# eth_lan8742a_phy.net
KiCad netlist of a schematic drawn in Altium Designer
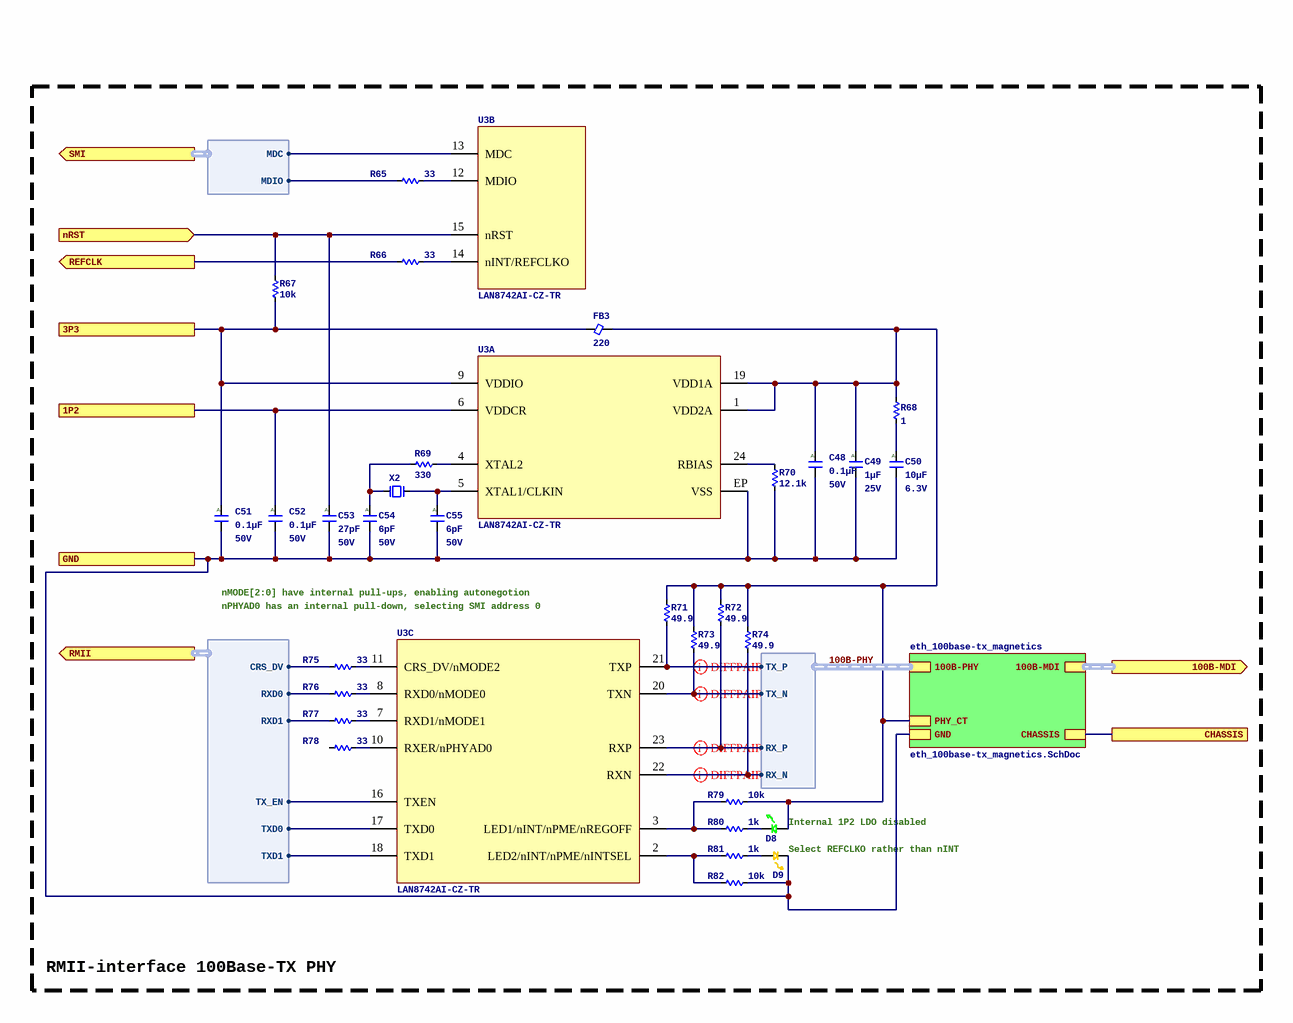
[diagram p0: eth_lan8742a_phy.SchDoc]

(export (version "E")
  (design (tool "Eeschema 10.0.6"))
  (components
    (comp (ref "C48")
      (value "CGA2B3X7R1H104M050BB")
      (footprint "C0402_0.55MM")
      (description "CAP CER 0.1UF 50V X7R 0402")
      (fields
        (field (name "CAPACITANCE") "0.1µF")
        (field (name "VOLTAGE - RATED") "50V")
        (field (name "TOLERANCE") "±20%")
        (field (name "MANUFACTURER") "TDK Corporation")
      )
      (libsource (lib "sscp") (part "__template_cap_auto"))
    )
    (comp (ref "C49")
      (value "CGJ3E1X7R1E105K080AC")
      (footprint "C0603_0.80MM")
      (description "CAP CER 1UF 25V X7R 0603")
      (fields
        (field (name "CAPACITANCE") "1µF")
        (field (name "VOLTAGE - RATED") "25V")
        (field (name "TOLERANCE") "±10%")
        (field (name "MANUFACTURER") "TDK Corporation")
      )
      (libsource (lib "sscp") (part "__template_cap_auto"))
    )
    (comp (ref "C50")
      (value "CGA4J1X7R0J106M125AC")
      (footprint "C0805_1.45MM")
      (description "CAP CER 10UF 6.3V X7R 0805")
      (fields
        (field (name "CAPACITANCE") "10µF")
        (field (name "VOLTAGE - RATED") "6.3V")
        (field (name "TOLERANCE") "±20%")
        (field (name "MANUFACTURER") "TDK Corporation")
      )
      (libsource (lib "sscp") (part "__template_cap_auto"))
    )
    (comp (ref "C51")
      (value "CGA2B3X7R1H104M050BB")
      (footprint "C0402_0.55MM")
      (description "CAP CER 0.1UF 50V X7R 0402")
      (fields
        (field (name "CAPACITANCE") "0.1µF")
        (field (name "VOLTAGE - RATED") "50V")
        (field (name "TOLERANCE") "±20%")
        (field (name "MANUFACTURER") "TDK Corporation")
      )
      (libsource (lib "sscp") (part "__template_cap_auto"))
    )
    (comp (ref "C52")
      (value "CGA2B3X7R1H104M050BB")
      (footprint "C0402_0.55MM")
      (description "CAP CER 0.1UF 50V X7R 0402")
      (fields
        (field (name "CAPACITANCE") "0.1µF")
        (field (name "VOLTAGE - RATED") "50V")
        (field (name "TOLERANCE") "±20%")
        (field (name "MANUFACTURER") "TDK Corporation")
      )
      (libsource (lib "sscp") (part "__template_cap_auto"))
    )
    (comp (ref "C53")
      (value "CGA2B2C0G1H270J050BA")
      (footprint "C0402_0.55MM")
      (description "CAP CER 27PF 50V C0G 0402")
      (fields
        (field (name "CAPACITANCE") "27pF")
        (field (name "VOLTAGE - RATED") "50V")
        (field (name "TOLERANCE") "±5%")
        (field (name "MANUFACTURER") "TDK Corporation")
      )
      (libsource (lib "sscp") (part "__template_cap_auto"))
    )
    (comp (ref "C54")
      (value "CGA2B2C0G1H060D050BA")
      (footprint "C0402_0.55MM")
      (description "CAP CER 6PF 50V C0G 0402")
      (fields
        (field (name "CAPACITANCE") "6pF")
        (field (name "VOLTAGE - RATED") "50V")
        (field (name "TOLERANCE") "±0.5pF")
        (field (name "MANUFACTURER") "TDK Corporation")
      )
      (libsource (lib "sscp") (part "__template_cap_auto"))
    )
    (comp (ref "C55")
      (value "CGA2B2C0G1H060D050BA")
      (footprint "C0402_0.55MM")
      (description "CAP CER 6PF 50V C0G 0402")
      (fields
        (field (name "CAPACITANCE") "6pF")
        (field (name "VOLTAGE - RATED") "50V")
        (field (name "TOLERANCE") "±0.5pF")
        (field (name "MANUFACTURER") "TDK Corporation")
      )
      (libsource (lib "sscp") (part "__template_cap_auto"))
    )
    (comp (ref "D8")
      (value "LTST-C190GKT")
      (footprint "LED_0603P_GREEN")
      (description "LED GREEN CLEAR 0603 SMD")
      (fields (field (name "MANUFACTURER") "Lite-On Inc"))
      (libsource (lib "SSCP") (part "LED_0603_GREEN_LTST-C190GKT"))
    )
    (comp (ref "D9")
      (value "LTST-C190AKT")
      (footprint "LED_0603P_AMBER")
      (description "LED AMBER CLEAR 0603 SMD")
      (fields (field (name "MANUFACTURER") "Lite-On Inc"))
      (libsource (lib "SSCP") (part "LED_0603_AMBER_LTST-C190AKT"))
    )
    (comp (ref "FB3")
      (value "MPZ1005S221ET000")
      (footprint "FB0402_0.55MM")
      (description "FERRITE BEAD 220 OHM 0402 1LN")
      (fields
        (field (name "IMPEDANCE (OHMS @ 100MHZ)") "220")
        (field (name "MANUFACTURER") "TDK Corporation")
      )
      (libsource (lib "sscp") (part "__template_ferrite"))
    )
    (comp (ref "R65")
      (value "ERJ-2RKF33R0X")
      (footprint "R0402_0.40MM")
      (description "RES SMD 33 OHM 1% 1/10W 0402")
      (fields
        (field (name "RESISTANCE") "33")
        (field (name "TOLERANCE") "±1%")
        (field (name "MANUFACTURER") "Panasonic Electronic Components")
      )
      (libsource (lib "sscp") (part "__template_resistor"))
    )
    (comp (ref "R66")
      (value "ERJ-2RKF33R0X")
      (footprint "R0402_0.40MM")
      (description "RES SMD 33 OHM 1% 1/10W 0402")
      (fields
        (field (name "RESISTANCE") "33")
        (field (name "TOLERANCE") "±1%")
        (field (name "MANUFACTURER") "Panasonic Electronic Components")
      )
      (libsource (lib "sscp") (part "__template_resistor"))
    )
    (comp (ref "R67")
      (value "ERJ-2RKF1002X")
      (footprint "R0402_0.40MM")
      (description "RES SMD 10K OHM 1% 1/10W 0402")
      (fields
        (field (name "RESISTANCE") "10k")
        (field (name "TOLERANCE") "±1%")
        (field (name "MANUFACTURER") "Panasonic Electronic Components")
      )
      (libsource (lib "sscp") (part "__template_resistor"))
    )
    (comp (ref "R68")
      (value "ERJ-2BQF1R0X")
      (footprint "R0402_0.40MM")
      (description "RES SMD 1 OHM 1% 1/6W 0402")
      (fields
        (field (name "RESISTANCE") "1")
        (field (name "TOLERANCE") "±1%")
        (field (name "MANUFACTURER") "Panasonic Electronic Components")
      )
      (libsource (lib "sscp") (part "__template_resistor"))
    )
    (comp (ref "R69")
      (value "ERJ-PA2F3300X")
      (footprint "R0402_0.40MM")
      (description "RES SMD 330 OHM 1% 1/5W 0402")
      (fields
        (field (name "RESISTANCE") "330")
        (field (name "TOLERANCE") "±1%")
        (field (name "MANUFACTURER") "Panasonic Electronic Components")
      )
      (libsource (lib "sscp") (part "__template_resistor"))
    )
    (comp (ref "R70")
      (value "ERJ-2RKF1212X")
      (footprint "R0402_0.40MM")
      (description "RES SMD 12.1K OHM 1% 1/10W 0402")
      (fields
        (field (name "RESISTANCE") "12.1k")
        (field (name "TOLERANCE") "±1%")
        (field (name "MANUFACTURER") "Panasonic Electronic Components")
      )
      (libsource (lib "sscp") (part "__template_resistor"))
    )
    (comp (ref "R71")
      (value "ERJ-2RKF49R9X")
      (footprint "R0402_0.40MM")
      (description "RES SMD 49.9 OHM 1% 1/10W 0402")
      (fields
        (field (name "RESISTANCE") "49.9")
        (field (name "TOLERANCE") "±1%")
        (field (name "MANUFACTURER") "Panasonic Electronic Components")
      )
      (libsource (lib "sscp") (part "__template_resistor"))
    )
    (comp (ref "R72")
      (value "ERJ-2RKF49R9X")
      (footprint "R0402_0.40MM")
      (description "RES SMD 49.9 OHM 1% 1/10W 0402")
      (fields
        (field (name "RESISTANCE") "49.9")
        (field (name "TOLERANCE") "±1%")
        (field (name "MANUFACTURER") "Panasonic Electronic Components")
      )
      (libsource (lib "sscp") (part "__template_resistor"))
    )
    (comp (ref "R73")
      (value "ERJ-2RKF49R9X")
      (footprint "R0402_0.40MM")
      (description "RES SMD 49.9 OHM 1% 1/10W 0402")
      (fields
        (field (name "RESISTANCE") "49.9")
        (field (name "TOLERANCE") "±1%")
        (field (name "MANUFACTURER") "Panasonic Electronic Components")
      )
      (libsource (lib "sscp") (part "__template_resistor"))
    )
    (comp (ref "R74")
      (value "ERJ-2RKF49R9X")
      (footprint "R0402_0.40MM")
      (description "RES SMD 49.9 OHM 1% 1/10W 0402")
      (fields
        (field (name "RESISTANCE") "49.9")
        (field (name "TOLERANCE") "±1%")
        (field (name "MANUFACTURER") "Panasonic Electronic Components")
      )
      (libsource (lib "sscp") (part "__template_resistor"))
    )
    (comp (ref "R75")
      (value "ERJ-2RKF33R0X")
      (footprint "R0402_0.40MM")
      (description "RES SMD 33 OHM 1% 1/10W 0402")
      (fields
        (field (name "RESISTANCE") "33")
        (field (name "TOLERANCE") "±1%")
        (field (name "MANUFACTURER") "Panasonic Electronic Components")
      )
      (libsource (lib "sscp") (part "__template_resistor"))
    )
    (comp (ref "R76")
      (value "ERJ-2RKF33R0X")
      (footprint "R0402_0.40MM")
      (description "RES SMD 33 OHM 1% 1/10W 0402")
      (fields
        (field (name "RESISTANCE") "33")
        (field (name "TOLERANCE") "±1%")
        (field (name "MANUFACTURER") "Panasonic Electronic Components")
      )
      (libsource (lib "sscp") (part "__template_resistor"))
    )
    (comp (ref "R77")
      (value "ERJ-2RKF33R0X")
      (footprint "R0402_0.40MM")
      (description "RES SMD 33 OHM 1% 1/10W 0402")
      (fields
        (field (name "RESISTANCE") "33")
        (field (name "TOLERANCE") "±1%")
        (field (name "MANUFACTURER") "Panasonic Electronic Components")
      )
      (libsource (lib "sscp") (part "__template_resistor"))
    )
    (comp (ref "R78")
      (value "ERJ-2RKF33R0X")
      (footprint "R0402_0.40MM")
      (description "RES SMD 33 OHM 1% 1/10W 0402")
      (fields
        (field (name "RESISTANCE") "33")
        (field (name "TOLERANCE") "±1%")
        (field (name "MANUFACTURER") "Panasonic Electronic Components")
      )
      (libsource (lib "sscp") (part "__template_resistor"))
    )
    (comp (ref "R79")
      (value "ERJ-2RKF1002X")
      (footprint "R0402_0.40MM")
      (description "RES SMD 10K OHM 1% 1/10W 0402")
      (fields
        (field (name "RESISTANCE") "10k")
        (field (name "TOLERANCE") "±1%")
        (field (name "MANUFACTURER") "Panasonic Electronic Components")
      )
      (libsource (lib "sscp") (part "__template_resistor"))
    )
    (comp (ref "R80")
      (value "ERJ-2RKF1001X")
      (footprint "R0402_0.40MM")
      (description "RES SMD 1K OHM 1% 1/10W 0402")
      (fields
        (field (name "RESISTANCE") "1k")
        (field (name "TOLERANCE") "±1%")
        (field (name "MANUFACTURER") "Panasonic Electronic Components")
      )
      (libsource (lib "sscp") (part "__template_resistor"))
    )
    (comp (ref "R81")
      (value "ERJ-2RKF1001X")
      (footprint "R0402_0.40MM")
      (description "RES SMD 1K OHM 1% 1/10W 0402")
      (fields
        (field (name "RESISTANCE") "1k")
        (field (name "TOLERANCE") "±1%")
        (field (name "MANUFACTURER") "Panasonic Electronic Components")
      )
      (libsource (lib "sscp") (part "__template_resistor"))
    )
    (comp (ref "R82")
      (value "ERJ-2RKF1002X")
      (footprint "R0402_0.40MM")
      (description "RES SMD 10K OHM 1% 1/10W 0402")
      (fields
        (field (name "RESISTANCE") "10k")
        (field (name "TOLERANCE") "±1%")
        (field (name "MANUFACTURER") "Panasonic Electronic Components")
      )
      (libsource (lib "sscp") (part "__template_resistor"))
    )
    (comp (ref "U3")
      (value "LAN8742AI-CZ-TR")
      (footprint "24QFN4E")
      (description "Ethernet Transceiver, PQCC24")
      (fields (field (name "MANUFACTURER") "Microchip"))
      (libsource (lib "SSCP") (part "ETH_PHY_LAN8742AI"))
    )
    (comp (ref "X2")
      (value "XTAL_XRCGB25M000F3A00R0")
      (footprint "4_SMD_2.0X1.6MM")
      (description "CRYSTAL 25.000MHZ 6PF SMD")
      (fields
        (field (name "MANUFACTURER") "Murata")
        (field (name "MANUFACTURER PART NUMBER") "XRCGB25M000F3A00R0")
      )
      (libsource (lib "SSCP") (part "XTAL_XRCGB25M000F3A00R0"))
    )
  )
  (nets
    (net (code "5") (name "/1P2") (class "Default")
      (node (ref "C52") (pin "1") (pintype "passive"))
      (node (ref "U3") (pin "6") (pinfunction "VDDCR_6") (pintype "passive"))
    )
    (net (code "6") (name "/3P3") (class "Default")
      (node (ref "C51") (pin "1") (pintype "passive"))
      (node (ref "FB3") (pin "1") (pintype "passive"))
      (node (ref "R67") (pin "1") (pintype "passive"))
      (node (ref "U3") (pin "9") (pinfunction "VDDIO_9") (pintype "passive"))
    )
    (net (code "10") (name "/CRS_DV") (class "Default") (node (ref "R75") (pin "2") (pintype "passive")))
    (net (code "11") (name "/GND") (class "Default")
      (node (ref "C48") (pin "2") (pintype "passive"))
      (node (ref "C49") (pin "2") (pintype "passive"))
      (node (ref "C50") (pin "2") (pintype "passive"))
      (node (ref "C51") (pin "2") (pintype "passive"))
      (node (ref "C52") (pin "2") (pintype "passive"))
      (node (ref "C53") (pin "2") (pintype "passive"))
      (node (ref "C54") (pin "2") (pintype "passive"))
      (node (ref "C55") (pin "2") (pintype "passive"))
      (node (ref "D9") (pin "1") (pintype "passive"))
      (node (ref "R70") (pin "2") (pintype "passive"))
      (node (ref "R82") (pin "2") (pintype "passive"))
      (node (ref "U3") (pin "EP") (pinfunction "VSS_EP") (pintype "passive"))
    )
    (net (code "12") (name "/MDC") (class "Default")
      (node (ref "U3") (pin "13") (pinfunction "MDC_13") (pintype "passive"))
    )
    (net (code "13") (name "/MDIO") (class "Default") (node (ref "R65") (pin "2") (pintype "passive")))
    (net (code "14") (name "/PHY_CT") (class "Default")
      (node (ref "C48") (pin "1") (pintype "passive"))
      (node (ref "C49") (pin "1") (pintype "passive"))
      (node (ref "D8") (pin "2") (pintype "passive"))
      (node (ref "FB3") (pin "2") (pintype "passive"))
      (node (ref "R68") (pin "2") (pintype "passive"))
      (node (ref "R71") (pin "1") (pintype "passive"))
      (node (ref "R72") (pin "1") (pintype "passive"))
      (node (ref "R73") (pin "1") (pintype "passive"))
      (node (ref "R74") (pin "1") (pintype "passive"))
      (node (ref "R79") (pin "2") (pintype "passive"))
      (node (ref "U3") (pin "1") (pinfunction "VDD2A_1") (pintype "passive"))
      (node (ref "U3") (pin "19") (pinfunction "VDD1A_19") (pintype "passive"))
    )
    (net (code "15") (name "/REFCLK") (class "Default") (node (ref "R66") (pin "2") (pintype "passive")))
    (net (code "16") (name "/RXD0") (class "Default") (node (ref "R76") (pin "2") (pintype "passive")))
    (net (code "17") (name "/RXD1") (class "Default") (node (ref "R77") (pin "2") (pintype "passive")))
    (net (code "18") (name "/RX_N") (class "Default")
      (node (ref "R74") (pin "2") (pintype "passive"))
      (node (ref "U3") (pin "22") (pinfunction "RXN_22") (pintype "passive"))
    )
    (net (code "19") (name "/RX_P") (class "Default")
      (node (ref "R72") (pin "2") (pintype "passive"))
      (node (ref "U3") (pin "23") (pinfunction "RXP_23") (pintype "passive"))
    )
    (net (code "20") (name "/TXD0") (class "Default")
      (node (ref "U3") (pin "17") (pinfunction "TXD0_17") (pintype "passive"))
    )
    (net (code "21") (name "/TXD1") (class "Default")
      (node (ref "U3") (pin "18") (pinfunction "TXD1_18") (pintype "passive"))
    )
    (net (code "22") (name "/TX_EN") (class "Default")
      (node (ref "U3") (pin "16") (pinfunction "TXEN_16") (pintype "passive"))
    )
    (net (code "23") (name "/TX_N") (class "Default")
      (node (ref "R73") (pin "2") (pintype "passive"))
      (node (ref "U3") (pin "20") (pinfunction "TXN_20") (pintype "passive"))
    )
    (net (code "24") (name "/TX_P") (class "Default")
      (node (ref "R71") (pin "2") (pintype "passive"))
      (node (ref "U3") (pin "21") (pinfunction "TXP_21") (pintype "passive"))
    )
    (net (code "25") (name "/nRST") (class "Default")
      (node (ref "C53") (pin "1") (pintype "passive"))
      (node (ref "R67") (pin "2") (pintype "passive"))
      (node (ref "U3") (pin "15") (pinfunction "nRST_15") (pintype "passive"))
    )
    (net (code "28") (name "Net-(C50-Pad1)") (class "Default")
      (node (ref "C50") (pin "1") (pintype "passive"))
      (node (ref "R68") (pin "1") (pintype "passive"))
    )
    (net (code "29") (name "Net-(C54-Pad1)") (class "Default")
      (node (ref "C54") (pin "1") (pintype "passive"))
      (node (ref "R69") (pin "1") (pintype "passive"))
      (node (ref "X2") (pin "3") (pinfunction "3_3") (pintype "passive"))
    )
    (net (code "30") (name "Net-(D8-Pad1)") (class "Default")
      (node (ref "D8") (pin "1") (pintype "passive"))
      (node (ref "R80") (pin "1") (pintype "passive"))
    )
    (net (code "31") (name "Net-(D9-Pad2)") (class "Default")
      (node (ref "D9") (pin "2") (pintype "passive"))
      (node (ref "R81") (pin "1") (pintype "passive"))
    )
    (net (code "32") (name "Net-(U3A-RBIAS)") (class "Default")
      (node (ref "R70") (pin "1") (pintype "passive"))
      (node (ref "U3") (pin "24") (pinfunction "RBIAS_24") (pintype "passive"))
    )
    (net (code "33") (name "Net-(U3A-XTAL1{slash}CLKIN)") (class "Default")
      (node (ref "C55") (pin "1") (pintype "passive"))
      (node (ref "U3") (pin "5") (pinfunction "XTAL1/CLKIN_5") (pintype "passive"))
      (node (ref "X2") (pin "1") (pinfunction "1_1") (pintype "passive"))
    )
    (net (code "34") (name "Net-(U3A-XTAL2)") (class "Default")
      (node (ref "R69") (pin "2") (pintype "passive"))
      (node (ref "U3") (pin "4") (pinfunction "XTAL2_4") (pintype "passive"))
    )
    (net (code "35") (name "Net-(U3B-MDIO)") (class "Default")
      (node (ref "R65") (pin "1") (pintype "passive"))
      (node (ref "U3") (pin "12") (pinfunction "MDIO_12") (pintype "passive"))
    )
    (net (code "36") (name "Net-(U3B-nINT{slash}REFCLKO)") (class "Default")
      (node (ref "R66") (pin "1") (pintype "passive"))
      (node (ref "U3") (pin "14") (pinfunction "nINT/REFCLKO_14") (pintype "passive"))
    )
    (net (code "37") (name "Net-(U3C-CRS_DV{slash}nMODE2)") (class "Default")
      (node (ref "R75") (pin "1") (pintype "passive"))
      (node (ref "U3") (pin "11") (pinfunction "CRS_DV/nMODE2_11") (pintype "passive"))
    )
    (net (code "38") (name "Net-(U3C-LED1{slash}nINT{slash}nPME{slash}nREGOFF)") (class "Default")
      (node (ref "R79") (pin "1") (pintype "passive"))
      (node (ref "R80") (pin "2") (pintype "passive"))
      (node (ref "U3") (pin "3") (pinfunction "LED1/nINT/nPME/nREGOFF_3") (pintype "passive"))
    )
    (net (code "39") (name "Net-(U3C-LED2{slash}nINT{slash}nPME{slash}nINTSEL)") (class "Default")
      (node (ref "R81") (pin "2") (pintype "passive"))
      (node (ref "R82") (pin "1") (pintype "passive"))
      (node (ref "U3") (pin "2") (pinfunction "LED2/nINT/nPME/nINTSEL_2") (pintype "passive"))
    )
    (net (code "40") (name "Net-(U3C-RXD0{slash}nMODE0)") (class "Default")
      (node (ref "R76") (pin "1") (pintype "passive"))
      (node (ref "U3") (pin "8") (pinfunction "RXD0/nMODE0_8") (pintype "passive"))
    )
    (net (code "41") (name "Net-(U3C-RXD1{slash}nMODE1)") (class "Default")
      (node (ref "R77") (pin "1") (pintype "passive"))
      (node (ref "U3") (pin "7") (pinfunction "RXD1/nMODE1_7") (pintype "passive"))
    )
    (net (code "42") (name "Net-(U3C-RXER{slash}nPHYAD0)") (class "Default")
      (node (ref "R78") (pin "1") (pintype "passive"))
      (node (ref "U3") (pin "10") (pinfunction "RXER/nPHYAD0_10") (pintype "passive"))
    )
    (net (code "43") (name "unconnected-(R78-Pad2)") (class "Default")
      (node (ref "R78") (pin "2") (pintype "passive"))
    )
  )
)
